# W025X.net
KiCad netlist of a schematic drawn in EAGLE
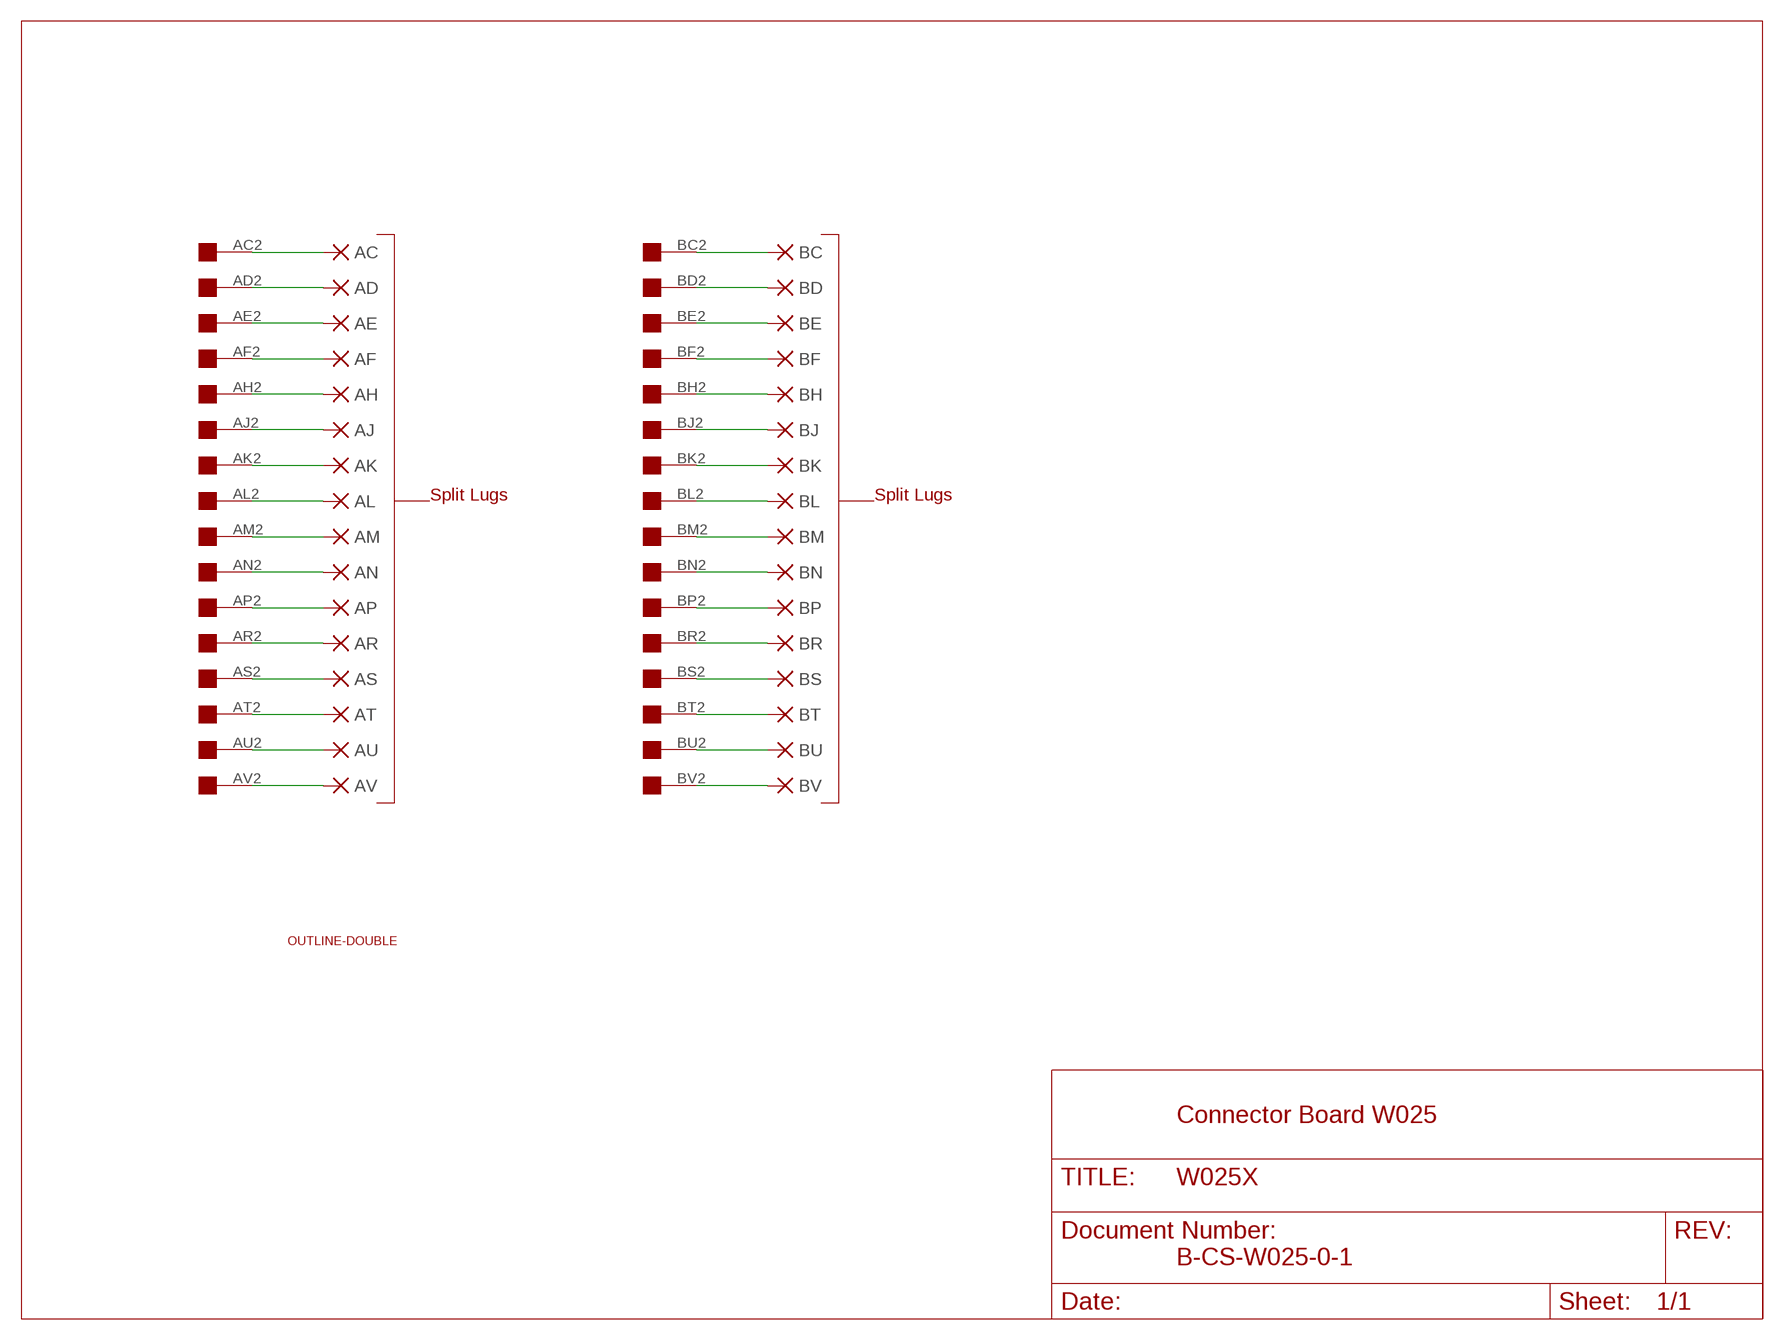
[diagram p0: schematic, sheet 1]

(export (version "E")
  (design (tool "Eeschema 10.0.6"))
  (components
    (comp (ref "AC")
      (value "PAD-0465")
      (footprint "eagle-import:0465")
      (libsource (lib "eagle-import") (part "PAD-0465"))
    )
    (comp (ref "AD")
      (value "PAD-0465")
      (footprint "eagle-import:0465")
      (libsource (lib "eagle-import") (part "PAD-0465"))
    )
    (comp (ref "AE")
      (value "PAD-0465")
      (footprint "eagle-import:0465")
      (libsource (lib "eagle-import") (part "PAD-0465"))
    )
    (comp (ref "AF")
      (value "PAD-0465")
      (footprint "eagle-import:0465")
      (libsource (lib "eagle-import") (part "PAD-0465"))
    )
    (comp (ref "AH")
      (value "PAD-0465")
      (footprint "eagle-import:0465")
      (libsource (lib "eagle-import") (part "PAD-0465"))
    )
    (comp (ref "AJ")
      (value "PAD-0465")
      (footprint "eagle-import:0465")
      (libsource (lib "eagle-import") (part "PAD-0465"))
    )
    (comp (ref "AK")
      (value "PAD-0465")
      (footprint "eagle-import:0465")
      (libsource (lib "eagle-import") (part "PAD-0465"))
    )
    (comp (ref "AL")
      (value "PAD-0465")
      (footprint "eagle-import:0465")
      (libsource (lib "eagle-import") (part "PAD-0465"))
    )
    (comp (ref "AM")
      (value "PAD-0465")
      (footprint "eagle-import:0465")
      (libsource (lib "eagle-import") (part "PAD-0465"))
    )
    (comp (ref "AN")
      (value "PAD-0465")
      (footprint "eagle-import:0465")
      (libsource (lib "eagle-import") (part "PAD-0465"))
    )
    (comp (ref "AP")
      (value "PAD-0465")
      (footprint "eagle-import:0465")
      (libsource (lib "eagle-import") (part "PAD-0465"))
    )
    (comp (ref "AR")
      (value "PAD-0465")
      (footprint "eagle-import:0465")
      (libsource (lib "eagle-import") (part "PAD-0465"))
    )
    (comp (ref "AS")
      (value "PAD-0465")
      (footprint "eagle-import:0465")
      (libsource (lib "eagle-import") (part "PAD-0465"))
    )
    (comp (ref "AT")
      (value "PAD-0465")
      (footprint "eagle-import:0465")
      (libsource (lib "eagle-import") (part "PAD-0465"))
    )
    (comp (ref "AU")
      (value "PAD-0465")
      (footprint "eagle-import:0465")
      (libsource (lib "eagle-import") (part "PAD-0465"))
    )
    (comp (ref "AV")
      (value "PAD-0465")
      (footprint "eagle-import:0465")
      (libsource (lib "eagle-import") (part "PAD-0465"))
    )
    (comp (ref "BC")
      (value "PAD-0465")
      (footprint "eagle-import:0465")
      (libsource (lib "eagle-import") (part "PAD-0465"))
    )
    (comp (ref "BD")
      (value "PAD-0465")
      (footprint "eagle-import:0465")
      (libsource (lib "eagle-import") (part "PAD-0465"))
    )
    (comp (ref "BE")
      (value "PAD-0465")
      (footprint "eagle-import:0465")
      (libsource (lib "eagle-import") (part "PAD-0465"))
    )
    (comp (ref "BF")
      (value "PAD-0465")
      (footprint "eagle-import:0465")
      (libsource (lib "eagle-import") (part "PAD-0465"))
    )
    (comp (ref "BH")
      (value "PAD-0465")
      (footprint "eagle-import:0465")
      (libsource (lib "eagle-import") (part "PAD-0465"))
    )
    (comp (ref "BJ")
      (value "PAD-0465")
      (footprint "eagle-import:0465")
      (libsource (lib "eagle-import") (part "PAD-0465"))
    )
    (comp (ref "BK")
      (value "PAD-0465")
      (footprint "eagle-import:0465")
      (libsource (lib "eagle-import") (part "PAD-0465"))
    )
    (comp (ref "BL")
      (value "PAD-0465")
      (footprint "eagle-import:0465")
      (libsource (lib "eagle-import") (part "PAD-0465"))
    )
    (comp (ref "BM")
      (value "PAD-0465")
      (footprint "eagle-import:0465")
      (libsource (lib "eagle-import") (part "PAD-0465"))
    )
    (comp (ref "BN")
      (value "PAD-0465")
      (footprint "eagle-import:0465")
      (libsource (lib "eagle-import") (part "PAD-0465"))
    )
    (comp (ref "BP")
      (value "PAD-0465")
      (footprint "eagle-import:0465")
      (libsource (lib "eagle-import") (part "PAD-0465"))
    )
    (comp (ref "BR")
      (value "PAD-0465")
      (footprint "eagle-import:0465")
      (libsource (lib "eagle-import") (part "PAD-0465"))
    )
    (comp (ref "BS")
      (value "PAD-0465")
      (footprint "eagle-import:0465")
      (libsource (lib "eagle-import") (part "PAD-0465"))
    )
    (comp (ref "BT")
      (value "PAD-0465")
      (footprint "eagle-import:0465")
      (libsource (lib "eagle-import") (part "PAD-0465"))
    )
    (comp (ref "BU")
      (value "PAD-0465")
      (footprint "eagle-import:0465")
      (libsource (lib "eagle-import") (part "PAD-0465"))
    )
    (comp (ref "BV")
      (value "PAD-0465")
      (footprint "eagle-import:0465")
      (libsource (lib "eagle-import") (part "PAD-0465"))
    )
    (comp (ref "U$1")
      (value "OUTLINE-DOUBLE")
      (footprint "eagle-import:DOUBLE")
      (libsource (lib "eagle-import") (part "OUTLINE-DOUBLE"))
    )
    (comp (ref "U$3")
      (value "DOUBLE")
      (footprint "eagle-import:EDGE-CON4")
      (libsource (lib "eagle-import") (part "DOUBLE"))
    )
  )
  (nets
    (net (code "1") (name "Net-(AC-P)") (class "Default")
      (node (ref "AC") (pin "P$1") (pinfunction "P_P$1") (pintype "passive"))
      (node (ref "U$3") (pin "AC2") (pinfunction "1_AC2") (pintype "bidirectional"))
    )
    (net (code "2") (name "Net-(AD-P)") (class "Default")
      (node (ref "AD") (pin "P$1") (pinfunction "P_P$1") (pintype "passive"))
      (node (ref "U$3") (pin "AD2") (pinfunction "1_AD2") (pintype "bidirectional"))
    )
    (net (code "3") (name "Net-(AE-P)") (class "Default")
      (node (ref "AE") (pin "P$1") (pinfunction "P_P$1") (pintype "passive"))
      (node (ref "U$3") (pin "AE2") (pinfunction "1_AE2") (pintype "bidirectional"))
    )
    (net (code "4") (name "Net-(AF-P)") (class "Default")
      (node (ref "AF") (pin "P$1") (pinfunction "P_P$1") (pintype "passive"))
      (node (ref "U$3") (pin "AF2") (pinfunction "1_AF2") (pintype "bidirectional"))
    )
    (net (code "5") (name "Net-(AH-P)") (class "Default")
      (node (ref "AH") (pin "P$1") (pinfunction "P_P$1") (pintype "passive"))
      (node (ref "U$3") (pin "AH2") (pinfunction "1_AH2") (pintype "bidirectional"))
    )
    (net (code "6") (name "Net-(AJ-P)") (class "Default")
      (node (ref "AJ") (pin "P$1") (pinfunction "P_P$1") (pintype "passive"))
      (node (ref "U$3") (pin "AJ2") (pinfunction "1_AJ2") (pintype "bidirectional"))
    )
    (net (code "7") (name "Net-(AK-P)") (class "Default")
      (node (ref "AK") (pin "P$1") (pinfunction "P_P$1") (pintype "passive"))
      (node (ref "U$3") (pin "AK2") (pinfunction "1_AK2") (pintype "bidirectional"))
    )
    (net (code "8") (name "Net-(AL-P)") (class "Default")
      (node (ref "AL") (pin "P$1") (pinfunction "P_P$1") (pintype "passive"))
      (node (ref "U$3") (pin "AL2") (pinfunction "1_AL2") (pintype "bidirectional"))
    )
    (net (code "9") (name "Net-(AM-P)") (class "Default")
      (node (ref "AM") (pin "P$1") (pinfunction "P_P$1") (pintype "passive"))
      (node (ref "U$3") (pin "AM2") (pinfunction "1_AM2") (pintype "bidirectional"))
    )
    (net (code "10") (name "Net-(AN-P)") (class "Default")
      (node (ref "AN") (pin "P$1") (pinfunction "P_P$1") (pintype "passive"))
      (node (ref "U$3") (pin "AN2") (pinfunction "1_AN2") (pintype "bidirectional"))
    )
    (net (code "11") (name "Net-(AP-P)") (class "Default")
      (node (ref "AP") (pin "P$1") (pinfunction "P_P$1") (pintype "passive"))
      (node (ref "U$3") (pin "AP2") (pinfunction "1_AP2") (pintype "bidirectional"))
    )
    (net (code "12") (name "Net-(AR-P)") (class "Default")
      (node (ref "AR") (pin "P$1") (pinfunction "P_P$1") (pintype "passive"))
      (node (ref "U$3") (pin "AR2") (pinfunction "1_AR2") (pintype "bidirectional"))
    )
    (net (code "13") (name "Net-(AS-P)") (class "Default")
      (node (ref "AS") (pin "P$1") (pinfunction "P_P$1") (pintype "passive"))
      (node (ref "U$3") (pin "AS2") (pinfunction "1_AS2") (pintype "bidirectional"))
    )
    (net (code "14") (name "Net-(AT-P)") (class "Default")
      (node (ref "AT") (pin "P$1") (pinfunction "P_P$1") (pintype "passive"))
      (node (ref "U$3") (pin "AT2") (pinfunction "1_AT2") (pintype "bidirectional"))
    )
    (net (code "15") (name "Net-(AU-P)") (class "Default")
      (node (ref "AU") (pin "P$1") (pinfunction "P_P$1") (pintype "passive"))
      (node (ref "U$3") (pin "AU2") (pinfunction "1_AU2") (pintype "bidirectional"))
    )
    (net (code "16") (name "Net-(AV-P)") (class "Default")
      (node (ref "AV") (pin "P$1") (pinfunction "P_P$1") (pintype "passive"))
      (node (ref "U$3") (pin "AV2") (pinfunction "1_AV2") (pintype "bidirectional"))
    )
    (net (code "17") (name "Net-(BC-P)") (class "Default")
      (node (ref "BC") (pin "P$1") (pinfunction "P_P$1") (pintype "passive"))
      (node (ref "U$3") (pin "BC2") (pinfunction "1_BC2") (pintype "bidirectional"))
    )
    (net (code "18") (name "Net-(BD-P)") (class "Default")
      (node (ref "BD") (pin "P$1") (pinfunction "P_P$1") (pintype "passive"))
      (node (ref "U$3") (pin "BD2") (pinfunction "1_BD2") (pintype "bidirectional"))
    )
    (net (code "19") (name "Net-(BE-P)") (class "Default")
      (node (ref "BE") (pin "P$1") (pinfunction "P_P$1") (pintype "passive"))
      (node (ref "U$3") (pin "BE2") (pinfunction "1_BE2") (pintype "bidirectional"))
    )
    (net (code "20") (name "Net-(BF-P)") (class "Default")
      (node (ref "BF") (pin "P$1") (pinfunction "P_P$1") (pintype "passive"))
      (node (ref "U$3") (pin "BF2") (pinfunction "1_BF2") (pintype "bidirectional"))
    )
    (net (code "21") (name "Net-(BH-P)") (class "Default")
      (node (ref "BH") (pin "P$1") (pinfunction "P_P$1") (pintype "passive"))
      (node (ref "U$3") (pin "BH2") (pinfunction "1_BH2") (pintype "bidirectional"))
    )
    (net (code "22") (name "Net-(BJ-P)") (class "Default")
      (node (ref "BJ") (pin "P$1") (pinfunction "P_P$1") (pintype "passive"))
      (node (ref "U$3") (pin "BJ2") (pinfunction "1_BJ2") (pintype "bidirectional"))
    )
    (net (code "23") (name "Net-(BK-P)") (class "Default")
      (node (ref "BK") (pin "P$1") (pinfunction "P_P$1") (pintype "passive"))
      (node (ref "U$3") (pin "BK2") (pinfunction "1_BK2") (pintype "bidirectional"))
    )
    (net (code "24") (name "Net-(BL-P)") (class "Default")
      (node (ref "BL") (pin "P$1") (pinfunction "P_P$1") (pintype "passive"))
      (node (ref "U$3") (pin "BL2") (pinfunction "1_BL2") (pintype "bidirectional"))
    )
    (net (code "25") (name "Net-(BM-P)") (class "Default")
      (node (ref "BM") (pin "P$1") (pinfunction "P_P$1") (pintype "passive"))
      (node (ref "U$3") (pin "BM2") (pinfunction "1_BM2") (pintype "bidirectional"))
    )
    (net (code "26") (name "Net-(BN-P)") (class "Default")
      (node (ref "BN") (pin "P$1") (pinfunction "P_P$1") (pintype "passive"))
      (node (ref "U$3") (pin "BN2") (pinfunction "1_BN2") (pintype "bidirectional"))
    )
    (net (code "27") (name "Net-(BP-P)") (class "Default")
      (node (ref "BP") (pin "P$1") (pinfunction "P_P$1") (pintype "passive"))
      (node (ref "U$3") (pin "BP2") (pinfunction "1_BP2") (pintype "bidirectional"))
    )
    (net (code "28") (name "Net-(BR-P)") (class "Default")
      (node (ref "BR") (pin "P$1") (pinfunction "P_P$1") (pintype "passive"))
      (node (ref "U$3") (pin "BR2") (pinfunction "1_BR2") (pintype "bidirectional"))
    )
    (net (code "29") (name "Net-(BS-P)") (class "Default")
      (node (ref "BS") (pin "P$1") (pinfunction "P_P$1") (pintype "passive"))
      (node (ref "U$3") (pin "BS2") (pinfunction "1_BS2") (pintype "bidirectional"))
    )
    (net (code "30") (name "Net-(BT-P)") (class "Default")
      (node (ref "BT") (pin "P$1") (pinfunction "P_P$1") (pintype "passive"))
      (node (ref "U$3") (pin "BT2") (pinfunction "1_BT2") (pintype "bidirectional"))
    )
    (net (code "31") (name "Net-(BU-P)") (class "Default")
      (node (ref "BU") (pin "P$1") (pinfunction "P_P$1") (pintype "passive"))
      (node (ref "U$3") (pin "BU2") (pinfunction "1_BU2") (pintype "bidirectional"))
    )
    (net (code "32") (name "Net-(BV-P)") (class "Default")
      (node (ref "BV") (pin "P$1") (pinfunction "P_P$1") (pintype "passive"))
      (node (ref "U$3") (pin "BV2") (pinfunction "1_BV2") (pintype "bidirectional"))
    )
  )
)
